# NusbioMCU.net
KiCad netlist of a schematic drawn in EAGLE
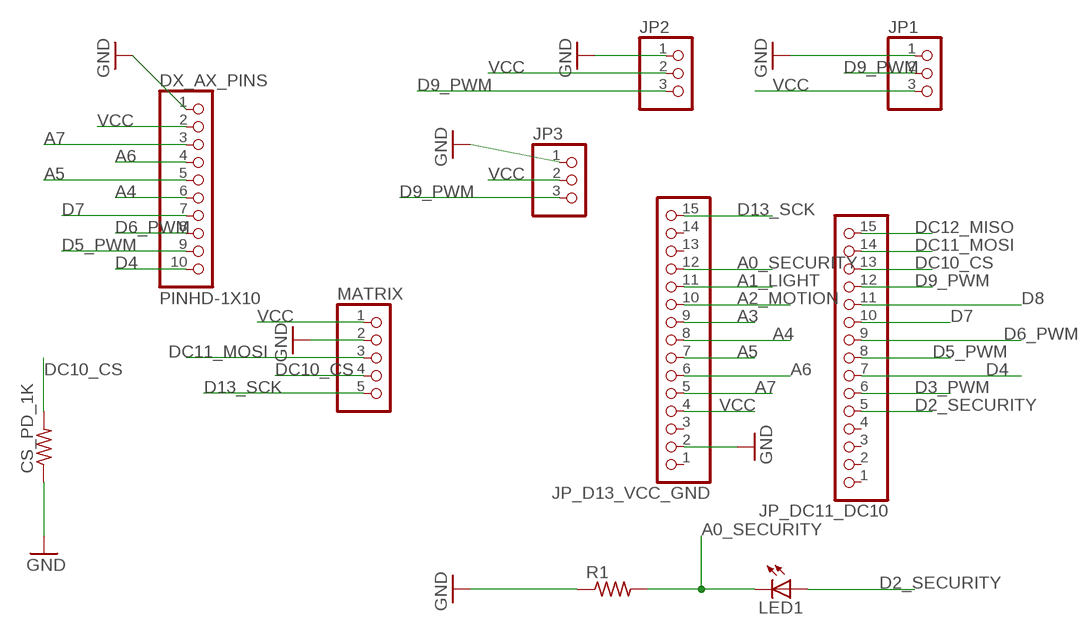
[diagram p0: schematic, sheet 1]

(export (version "E")
  (design (tool "Eeschema 10.0.6"))
  (components
    (comp (ref "CS_PD_1K")
      (value "R-US_R0805")
      (footprint "eagle-import:R0805")
      (libsource (lib "eagle-import") (part "R-US_R0805"))
    )
    (comp (ref "DX_AX_PINS")
      (value "PINHD-1X10")
      (footprint "eagle-import:1X10-BIG")
      (libsource (lib "eagle-import") (part "PINHD-1X10"))
    )
    (comp (ref "JP1")
      (value "PINHD-1X3")
      (footprint "eagle-import:1X03")
      (libsource (lib "eagle-import") (part "PINHD-1X3"))
    )
    (comp (ref "JP2")
      (value "PINHD-1X3")
      (footprint "eagle-import:1X03")
      (libsource (lib "eagle-import") (part "PINHD-1X3"))
    )
    (comp (ref "JP3")
      (value "PINHD-1X3")
      (footprint "eagle-import:1X03")
      (libsource (lib "eagle-import") (part "PINHD-1X3"))
    )
    (comp (ref "JP_D13_VCC_GND")
      (value "PINHD-1X15")
      (footprint "eagle-import:1X15")
      (libsource (lib "eagle-import") (part "PINHD-1X15"))
    )
    (comp (ref "JP_DC11_DC10")
      (value "PINHD-1X15")
      (footprint "eagle-import:1X15")
      (libsource (lib "eagle-import") (part "PINHD-1X15"))
    )
    (comp (ref "LED1")
      (value "LEDCHIPLED_0805")
      (footprint "eagle-import:CHIPLED_0805")
      (libsource (lib "eagle-import") (part "LEDCHIPLED_0805"))
    )
    (comp (ref "MATRIX")
      (value "PINHD-1X5")
      (footprint "eagle-import:1X05")
      (libsource (lib "eagle-import") (part "PINHD-1X5"))
    )
    (comp (ref "R1")
      (value "R-US_R0805")
      (footprint "eagle-import:R0805")
      (libsource (lib "eagle-import") (part "R-US_R0805"))
    )
  )
  (nets
    (net (code "1") (name "/A0_SECURITY") (class "Default")
      (node (ref "JP_D13_VCC_GND") (pin "12") (pinfunction "12_12") (pintype "passive"))
      (node (ref "LED1") (pin "C") (pinfunction "C_C") (pintype "passive"))
      (node (ref "R1") (pin "2") (pinfunction "2_2") (pintype "passive"))
    )
    (net (code "2") (name "/A1_LIGHT") (class "Default")
      (node (ref "JP_D13_VCC_GND") (pin "11") (pinfunction "11_11") (pintype "passive"))
    )
    (net (code "3") (name "/A2_MOTION") (class "Default")
      (node (ref "JP_D13_VCC_GND") (pin "10") (pinfunction "10_10") (pintype "passive"))
    )
    (net (code "4") (name "/A3") (class "Default")
      (node (ref "JP_D13_VCC_GND") (pin "9") (pinfunction "9_9") (pintype "passive"))
    )
    (net (code "5") (name "/A4") (class "Default")
      (node (ref "DX_AX_PINS") (pin "6") (pinfunction "6_6") (pintype "passive"))
      (node (ref "JP_D13_VCC_GND") (pin "8") (pinfunction "8_8") (pintype "passive"))
    )
    (net (code "6") (name "/A5") (class "Default")
      (node (ref "DX_AX_PINS") (pin "5") (pinfunction "5_5") (pintype "passive"))
      (node (ref "JP_D13_VCC_GND") (pin "7") (pinfunction "7_7") (pintype "passive"))
    )
    (net (code "7") (name "/A6") (class "Default")
      (node (ref "DX_AX_PINS") (pin "4") (pinfunction "4_4") (pintype "passive"))
      (node (ref "JP_D13_VCC_GND") (pin "6") (pinfunction "6_6") (pintype "passive"))
    )
    (net (code "8") (name "/A7") (class "Default")
      (node (ref "DX_AX_PINS") (pin "3") (pinfunction "3_3") (pintype "passive"))
      (node (ref "JP_D13_VCC_GND") (pin "5") (pinfunction "5_5") (pintype "passive"))
    )
    (net (code "9") (name "/D2_SECURITY") (class "Default")
      (node (ref "JP_DC11_DC10") (pin "5") (pinfunction "5_5") (pintype "passive"))
      (node (ref "LED1") (pin "A") (pinfunction "A_A") (pintype "passive"))
    )
    (net (code "10") (name "/D3_PWM") (class "Default")
      (node (ref "JP_DC11_DC10") (pin "6") (pinfunction "6_6") (pintype "passive"))
    )
    (net (code "11") (name "/D4") (class "Default")
      (node (ref "DX_AX_PINS") (pin "10") (pinfunction "10_10") (pintype "passive"))
      (node (ref "JP_DC11_DC10") (pin "7") (pinfunction "7_7") (pintype "passive"))
    )
    (net (code "12") (name "/D5_PWM") (class "Default")
      (node (ref "DX_AX_PINS") (pin "9") (pinfunction "9_9") (pintype "passive"))
      (node (ref "JP_DC11_DC10") (pin "8") (pinfunction "8_8") (pintype "passive"))
    )
    (net (code "13") (name "/D6_PWM") (class "Default")
      (node (ref "DX_AX_PINS") (pin "8") (pinfunction "8_8") (pintype "passive"))
      (node (ref "JP_DC11_DC10") (pin "9") (pinfunction "9_9") (pintype "passive"))
    )
    (net (code "14") (name "/D7") (class "Default")
      (node (ref "DX_AX_PINS") (pin "7") (pinfunction "7_7") (pintype "passive"))
      (node (ref "JP_DC11_DC10") (pin "10") (pinfunction "10_10") (pintype "passive"))
    )
    (net (code "15") (name "/D8") (class "Default")
      (node (ref "JP_DC11_DC10") (pin "11") (pinfunction "11_11") (pintype "passive"))
    )
    (net (code "16") (name "/D9_PWM") (class "Default")
      (node (ref "JP1") (pin "2") (pinfunction "2_2") (pintype "passive"))
      (node (ref "JP2") (pin "3") (pinfunction "3_3") (pintype "passive"))
      (node (ref "JP3") (pin "3") (pinfunction "3_3") (pintype "passive"))
      (node (ref "JP_DC11_DC10") (pin "12") (pinfunction "12_12") (pintype "passive"))
    )
    (net (code "17") (name "/D13_SCK") (class "Default")
      (node (ref "JP_D13_VCC_GND") (pin "15") (pinfunction "15_15") (pintype "passive"))
      (node (ref "MATRIX") (pin "5") (pinfunction "5_5") (pintype "passive"))
    )
    (net (code "18") (name "/DC10_CS") (class "Default")
      (node (ref "CS_PD_1K") (pin "2") (pinfunction "2_2") (pintype "passive"))
      (node (ref "JP_DC11_DC10") (pin "13") (pinfunction "13_13") (pintype "passive"))
      (node (ref "MATRIX") (pin "4") (pinfunction "4_4") (pintype "passive"))
    )
    (net (code "19") (name "/DC11_MOSI") (class "Default")
      (node (ref "JP_DC11_DC10") (pin "14") (pinfunction "14_14") (pintype "passive"))
      (node (ref "MATRIX") (pin "3") (pinfunction "3_3") (pintype "passive"))
    )
    (net (code "20") (name "/DC12_MISO") (class "Default")
      (node (ref "JP_DC11_DC10") (pin "15") (pinfunction "15_15") (pintype "passive"))
    )
    (net (code "21") (name "/VCC") (class "Default")
      (node (ref "DX_AX_PINS") (pin "2") (pinfunction "2_2") (pintype "passive"))
      (node (ref "JP1") (pin "3") (pinfunction "3_3") (pintype "passive"))
      (node (ref "JP2") (pin "2") (pinfunction "2_2") (pintype "passive"))
      (node (ref "JP3") (pin "2") (pinfunction "2_2") (pintype "passive"))
      (node (ref "JP_D13_VCC_GND") (pin "4") (pinfunction "4_4") (pintype "passive"))
      (node (ref "MATRIX") (pin "1") (pinfunction "1_1") (pintype "passive"))
    )
    (net (code "22") (name "GND") (class "Default")
      (node (ref "CS_PD_1K") (pin "1") (pinfunction "1_1") (pintype "passive"))
      (node (ref "DX_AX_PINS") (pin "1") (pinfunction "1_1") (pintype "passive"))
      (node (ref "JP1") (pin "1") (pinfunction "1_1") (pintype "passive"))
      (node (ref "JP2") (pin "1") (pinfunction "1_1") (pintype "passive"))
      (node (ref "JP3") (pin "1") (pinfunction "1_1") (pintype "passive"))
      (node (ref "JP_D13_VCC_GND") (pin "2") (pinfunction "2_2") (pintype "passive"))
      (node (ref "MATRIX") (pin "2") (pinfunction "2_2") (pintype "passive"))
      (node (ref "R1") (pin "1") (pinfunction "1_1") (pintype "passive"))
    )
    (net (code "23") (name "unconnected-(JP_D13_VCC_GND-Pad1)") (class "Default")
      (node (ref "JP_D13_VCC_GND") (pin "1") (pinfunction "1_1") (pintype "passive"))
    )
    (net (code "24") (name "unconnected-(JP_D13_VCC_GND-Pad3)") (class "Default")
      (node (ref "JP_D13_VCC_GND") (pin "3") (pinfunction "3_3") (pintype "passive"))
    )
    (net (code "25") (name "unconnected-(JP_D13_VCC_GND-Pad13)") (class "Default")
      (node (ref "JP_D13_VCC_GND") (pin "13") (pinfunction "13_13") (pintype "passive"))
    )
    (net (code "26") (name "unconnected-(JP_D13_VCC_GND-Pad14)") (class "Default")
      (node (ref "JP_D13_VCC_GND") (pin "14") (pinfunction "14_14") (pintype "passive"))
    )
    (net (code "27") (name "unconnected-(JP_DC11_DC10-Pad1)") (class "Default")
      (node (ref "JP_DC11_DC10") (pin "1") (pinfunction "1_1") (pintype "passive"))
    )
    (net (code "28") (name "unconnected-(JP_DC11_DC10-Pad2)") (class "Default")
      (node (ref "JP_DC11_DC10") (pin "2") (pinfunction "2_2") (pintype "passive"))
    )
    (net (code "29") (name "unconnected-(JP_DC11_DC10-Pad3)") (class "Default")
      (node (ref "JP_DC11_DC10") (pin "3") (pinfunction "3_3") (pintype "passive"))
    )
    (net (code "30") (name "unconnected-(JP_DC11_DC10-Pad4)") (class "Default")
      (node (ref "JP_DC11_DC10") (pin "4") (pinfunction "4_4") (pintype "passive"))
    )
  )
)
